# ws2811_eagle.net
KiCad netlist of a schematic drawn in EAGLE
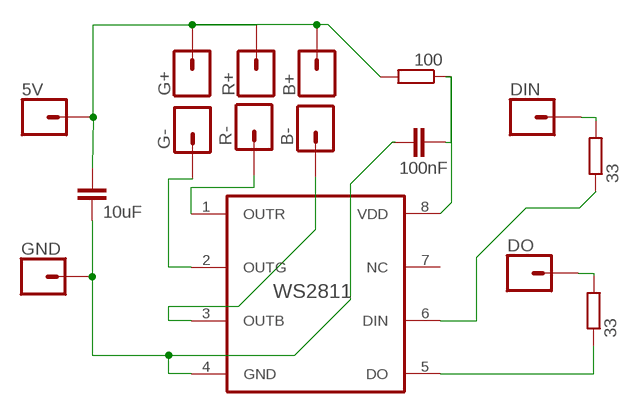
[diagram p0: schematic, sheet 1]

(export (version "E")
  (design (tool "Eeschema 10.0.6"))
  (components
    (comp (ref "5V")
      (value "1PIN")
      (footprint "eagle-import:1PIN_1.0MMCORE")
      (libsource (lib "eagle-import") (part "1PIN"))
    )
    (comp (ref "B+")
      (value "1PIN1PIN_0.8MMCORE")
      (footprint "eagle-import:1PIN_0.8MMCORE")
      (libsource (lib "eagle-import") (part "1PIN1PIN_0.8MMCORE"))
    )
    (comp (ref "B-")
      (value "1PIN1PIN_0.8MMCORE")
      (footprint "eagle-import:1PIN_0.8MMCORE")
      (libsource (lib "eagle-import") (part "1PIN1PIN_0.8MMCORE"))
    )
    (comp (ref "C1")
      (value "10uF")
      (footprint "eagle-import:C0805")
      (libsource (lib "eagle-import") (part "C-EUC0805"))
    )
    (comp (ref "C2")
      (value "100nF")
      (footprint "eagle-import:C0805")
      (libsource (lib "eagle-import") (part "C-EUC0805"))
    )
    (comp (ref "DIN")
      (value "1PIN")
      (footprint "eagle-import:1PIN_1.0MMCORE")
      (libsource (lib "eagle-import") (part "1PIN"))
    )
    (comp (ref "DO")
      (value "1PIN")
      (footprint "eagle-import:1PIN_1.0MMCORE")
      (libsource (lib "eagle-import") (part "1PIN"))
    )
    (comp (ref "G+")
      (value "1PIN1PIN_0.8MMCORE")
      (footprint "eagle-import:1PIN_0.8MMCORE")
      (libsource (lib "eagle-import") (part "1PIN1PIN_0.8MMCORE"))
    )
    (comp (ref "G-")
      (value "1PIN1PIN_0.8MMCORE")
      (footprint "eagle-import:1PIN_0.8MMCORE")
      (libsource (lib "eagle-import") (part "1PIN1PIN_0.8MMCORE"))
    )
    (comp (ref "GND")
      (value "1PIN")
      (footprint "eagle-import:1PIN_1.0MMCORE")
      (libsource (lib "eagle-import") (part "1PIN"))
    )
    (comp (ref "R+")
      (value "1PIN1PIN_0.8MMCORE")
      (footprint "eagle-import:1PIN_0.8MMCORE")
      (fields (field (name "SPICEPREFIX") "X"))
      (libsource (lib "eagle-import") (part "1PIN1PIN_0.8MMCORE"))
    )
    (comp (ref "R-")
      (value "1PIN1PIN_0.8MMCORE")
      (footprint "eagle-import:1PIN_0.8MMCORE")
      (libsource (lib "eagle-import") (part "1PIN1PIN_0.8MMCORE"))
    )
    (comp (ref "R1")
      (value "33")
      (footprint "eagle-import:R0805")
      (libsource (lib "eagle-import") (part "R-EU_R0805"))
    )
    (comp (ref "R2")
      (value "100")
      (footprint "eagle-import:R0805")
      (libsource (lib "eagle-import") (part "R-EU_R0805"))
    )
    (comp (ref "R3")
      (value "33")
      (footprint "eagle-import:R0805")
      (libsource (lib "eagle-import") (part "R-EU_R0805"))
    )
    (comp (ref "WS2811")
      (value "WS2811")
      (footprint "eagle-import:SO08")
      (libsource (lib "eagle-import") (part "WS2811"))
    )
  )
  (nets
    (net (code "1") (name "Net-(5V-Pad1)") (class "Default")
      (node (ref "5V") (pin "1") (pinfunction "1_1") (pintype "passive"))
      (node (ref "B+") (pin "1") (pinfunction "1_1") (pintype "passive"))
      (node (ref "C1") (pin "1") (pinfunction "1_1") (pintype "passive"))
      (node (ref "G+") (pin "1") (pinfunction "1_1") (pintype "passive"))
      (node (ref "R+") (pin "1") (pinfunction "1_1") (pintype "passive"))
      (node (ref "R2") (pin "2") (pinfunction "2_2") (pintype "passive"))
    )
    (net (code "2") (name "Net-(DIN-Pad1)") (class "Default")
      (node (ref "DIN") (pin "1") (pinfunction "1_1") (pintype "passive"))
      (node (ref "R1") (pin "2") (pinfunction "2_2") (pintype "passive"))
    )
    (net (code "3") (name "Net-(DO-Pad1)") (class "Default")
      (node (ref "DO") (pin "1") (pinfunction "1_1") (pintype "passive"))
      (node (ref "R3") (pin "2") (pinfunction "2_2") (pintype "passive"))
    )
    (net (code "4") (name "Net-(WS2811-DIN)") (class "Default")
      (node (ref "R1") (pin "1") (pinfunction "1_1") (pintype "passive"))
      (node (ref "WS2811") (pin "6") (pinfunction "DIN_6") (pintype "input"))
    )
    (net (code "5") (name "Net-(WS2811-DO)") (class "Default")
      (node (ref "R3") (pin "1") (pinfunction "1_1") (pintype "passive"))
      (node (ref "WS2811") (pin "5") (pinfunction "DO_5") (pintype "output"))
    )
    (net (code "6") (name "Net-(WS2811-GND)") (class "Default")
      (node (ref "C1") (pin "2") (pinfunction "2_2") (pintype "passive"))
      (node (ref "C2") (pin "1") (pinfunction "1_1") (pintype "passive"))
      (node (ref "GND") (pin "1") (pinfunction "1_1") (pintype "passive"))
      (node (ref "WS2811") (pin "4") (pinfunction "GND_4") (pintype "power_in"))
    )
    (net (code "7") (name "Net-(WS2811-OUTB)") (class "Default")
      (node (ref "B-") (pin "1") (pinfunction "1_1") (pintype "passive"))
      (node (ref "WS2811") (pin "3") (pinfunction "OUTB_3") (pintype "output"))
    )
    (net (code "8") (name "Net-(WS2811-OUTG)") (class "Default")
      (node (ref "G-") (pin "1") (pinfunction "1_1") (pintype "passive"))
      (node (ref "WS2811") (pin "2") (pinfunction "OUTG_2") (pintype "output"))
    )
    (net (code "9") (name "Net-(WS2811-OUTR)") (class "Default")
      (node (ref "R-") (pin "1") (pinfunction "1_1") (pintype "passive"))
      (node (ref "WS2811") (pin "1") (pinfunction "OUTR_1") (pintype "output"))
    )
    (net (code "10") (name "Net-(WS2811-VDD)") (class "Default")
      (node (ref "C2") (pin "2") (pinfunction "2_2") (pintype "passive"))
      (node (ref "R2") (pin "1") (pinfunction "1_1") (pintype "passive"))
      (node (ref "WS2811") (pin "8") (pinfunction "VDD_8") (pintype "power_in"))
    )
    (net (code "11") (name "unconnected-(WS2811-NC-Pad7)") (class "Default")
      (node (ref "WS2811") (pin "7") (pinfunction "NC_7") (pintype "no_connect"))
    )
  )
)
